# mux.net
KiCad netlist of a schematic drawn in Altium Designer
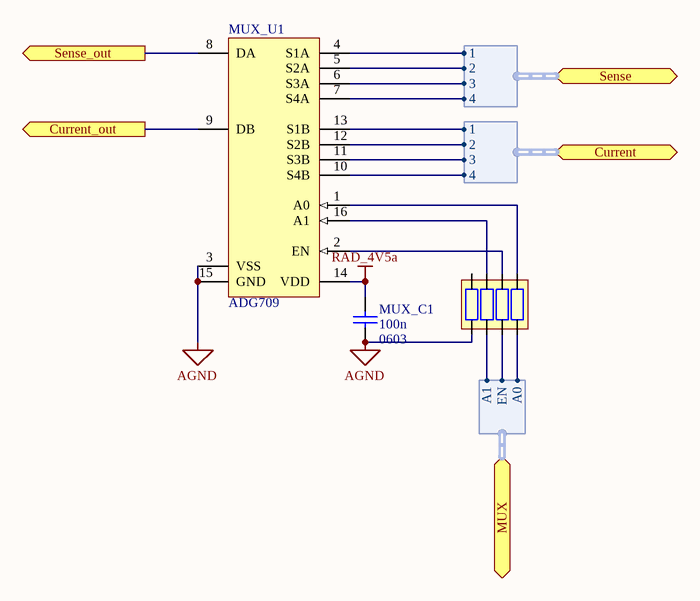
[diagram p0: mux.SchDoc]

(export (version "E")
  (design (tool "Eeschema 10.0.6"))
  (components
    (comp (ref "MUX_C1")
      (value "100n")
      (footprint "SMD_Capacitor_0603")
      (description "Cap")
      (fields (field (name "PACKAGE") "0603"))
      (libsource (lib "capacitors") (part "Cap"))
    )
    (comp (ref "MUX_R1")
      (value "YC124-JR-072K2L")
      (footprint "SMD_RESISTOR_ARRAY_YC124")
      (description "RESISTOR ARRAY, 4 x 0402")
      (libsource (lib "resistors") (part "YC124-JR-072K2L"))
    )
    (comp (ref "MUX_U1")
      (value "ADG709")
      (footprint "TSSOP16")
      (description "CMOS Analog 4-Channel Multiplexer")
      (fields (field (name "MANUFACTURER") "Analog Devices") (field (name "MANUFACTURERPARTNUMBER") "ADG709"))
      (libsource (lib "microcircuits") (part "ADG709"))
    )
  )
  (nets
    (net (code "3") (name "/A0") (class "Default")
      (node (ref "MUX_R1") (pin "4") (pinfunction "4_4") (pintype "passive"))
    )
    (net (code "4") (name "/A1") (class "Default")
      (node (ref "MUX_R1") (pin "2") (pinfunction "2_2") (pintype "passive"))
    )
    (net (code "5") (name "/Current_out") (class "Default")
      (node (ref "MUX_U1") (pin "9") (pinfunction "DB_9") (pintype "passive"))
    )
    (net (code "6") (name "/EN") (class "Default")
      (node (ref "MUX_R1") (pin "3") (pinfunction "3_3") (pintype "passive"))
    )
    (net (code "7") (name "/Sense_out") (class "Default")
      (node (ref "MUX_U1") (pin "8") (pinfunction "DA_8") (pintype "passive"))
    )
    (net (code "10") (name "AGND") (class "Default")
      (node (ref "MUX_C1") (pin "2") (pinfunction "2_2") (pintype "passive"))
      (node (ref "MUX_R1") (pin "1") (pinfunction "1_1") (pintype "passive"))
      (node (ref "MUX_U1") (pin "15") (pinfunction "GND_15") (pintype "power_in"))
      (node (ref "MUX_U1") (pin "3") (pinfunction "VSS_3") (pintype "power_in"))
    )
    (net (code "11") (name "Net-(MUX_U1-A0)") (class "Default")
      (node (ref "MUX_R1") (pin "5") (pinfunction "5_5") (pintype "passive"))
      (node (ref "MUX_U1") (pin "1") (pinfunction "A0_1") (pintype "input"))
    )
    (net (code "12") (name "Net-(MUX_U1-A1)") (class "Default")
      (node (ref "MUX_R1") (pin "7") (pinfunction "7_7") (pintype "passive"))
      (node (ref "MUX_U1") (pin "16") (pinfunction "A1_16") (pintype "input"))
    )
    (net (code "13") (name "Net-(MUX_U1-EN)") (class "Default")
      (node (ref "MUX_R1") (pin "6") (pinfunction "6_6") (pintype "passive"))
      (node (ref "MUX_U1") (pin "2") (pinfunction "EN_2") (pintype "input"))
    )
    (net (code "14") (name "RAD_4V5a") (class "Default")
      (node (ref "MUX_C1") (pin "1") (pinfunction "1_1") (pintype "passive"))
      (node (ref "MUX_U1") (pin "14") (pinfunction "VDD_14") (pintype "power_in"))
    )
    (net (code "15") (name "unconnected-(MUX_R1-Pad8)") (class "Default")
      (node (ref "MUX_R1") (pin "8") (pinfunction "8_8") (pintype "passive"))
    )
    (net (code "16") (name "unconnected-(MUX_U1-S1A-Pad4)") (class "Default")
      (node (ref "MUX_U1") (pin "4") (pinfunction "S1A_4") (pintype "passive"))
    )
    (net (code "17") (name "unconnected-(MUX_U1-S1B-Pad13)") (class "Default")
      (node (ref "MUX_U1") (pin "13") (pinfunction "S1B_13") (pintype "passive"))
    )
    (net (code "18") (name "unconnected-(MUX_U1-S2A-Pad5)") (class "Default")
      (node (ref "MUX_U1") (pin "5") (pinfunction "S2A_5") (pintype "passive"))
    )
    (net (code "19") (name "unconnected-(MUX_U1-S2B-Pad12)") (class "Default")
      (node (ref "MUX_U1") (pin "12") (pinfunction "S2B_12") (pintype "passive"))
    )
    (net (code "20") (name "unconnected-(MUX_U1-S3A-Pad6)") (class "Default")
      (node (ref "MUX_U1") (pin "6") (pinfunction "S3A_6") (pintype "passive"))
    )
    (net (code "21") (name "unconnected-(MUX_U1-S3B-Pad11)") (class "Default")
      (node (ref "MUX_U1") (pin "11") (pinfunction "S3B_11") (pintype "passive"))
    )
    (net (code "22") (name "unconnected-(MUX_U1-S4A-Pad7)") (class "Default")
      (node (ref "MUX_U1") (pin "7") (pinfunction "S4A_7") (pintype "passive"))
    )
    (net (code "23") (name "unconnected-(MUX_U1-S4B-Pad10)") (class "Default")
      (node (ref "MUX_U1") (pin "10") (pinfunction "S4B_10") (pintype "passive"))
    )
  )
)
